# Overview.net
KiCad netlist of a schematic drawn in Altium Designer
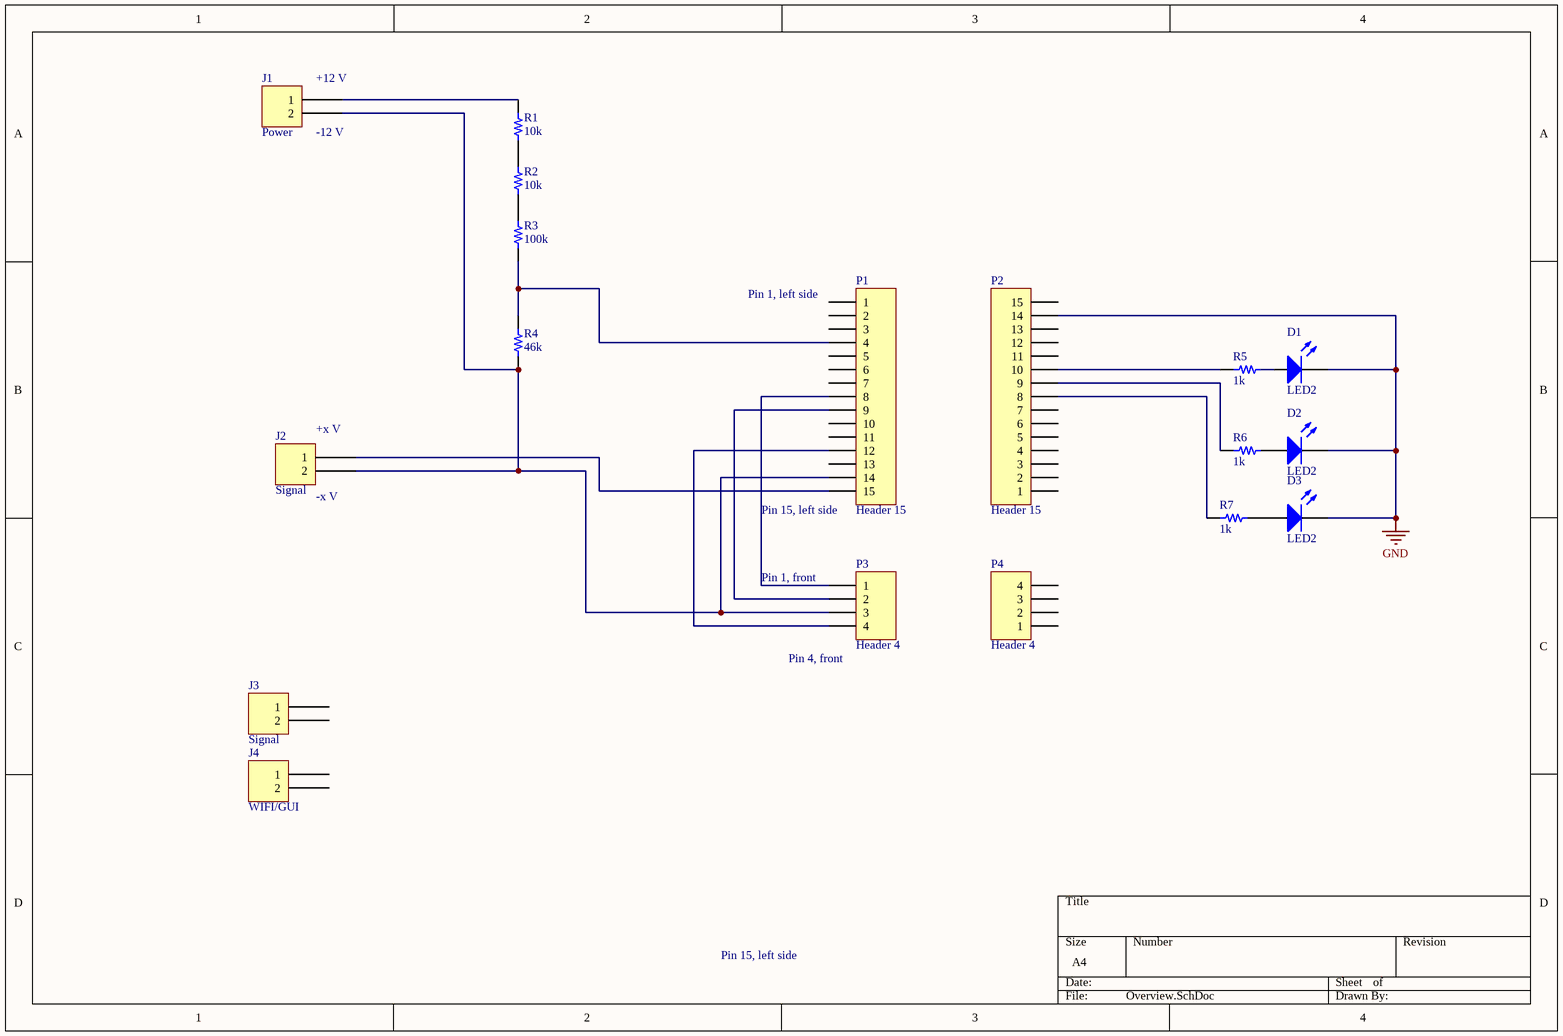
[diagram p0: Overview.SchDoc]

(export (version "E")
  (design (tool "Eeschema 10.0.6"))
  (components
    (comp (ref "D1")
      (value "LED2")
      (footprint "3.2X1.6X1.1")
      (description "RED")
      (fields (field (name "PUBLISHER") "Altium Limited"))
      (libsource (lib "Miscellaneous Devices") (part "LED2"))
    )
    (comp (ref "D2")
      (value "LED2")
      (footprint "3.2X1.6X1.1")
      (description "GREEN")
      (fields (field (name "PUBLISHER") "Altium Limited"))
      (libsource (lib "Miscellaneous Devices") (part "LED2"))
    )
    (comp (ref "D3")
      (value "LED2")
      (footprint "3.2X1.6X1.1")
      (description "YELLOW")
      (fields (field (name "PUBLISHER") "Altium Limited"))
      (libsource (lib "Miscellaneous Devices") (part "LED2"))
    )
    (comp (ref "J1")
      (value "Power")
      (footprint "JST XH B2B-XH-A")
      (description "CONN HEADER XH TOP 2POS 2.5MM")
      (fields
        (field (name "PART NUMBER") "B2B-XH-A(LF)(SN)")
        (field (name "MANUFACTURER") "JST Sales America Inc.")
      )
      (libsource (lib "Celestial Library Database") (part "2 Pin"))
    )
    (comp (ref "J2")
      (value "Signal")
      (footprint "JST XH B2B-XH-A")
      (description "CONN HEADER XH TOP 2POS 2.5MM")
      (fields
        (field (name "PART NUMBER") "B2B-XH-A(LF)(SN)")
        (field (name "MANUFACTURER") "JST Sales America Inc.")
      )
      (libsource (lib "Celestial Library Database") (part "2 Pin"))
    )
    (comp (ref "J3")
      (value "Signal")
      (footprint "JST XH B2B-XH-A")
      (description "CONN HEADER XH TOP 2POS 2.5MM")
      (fields
        (field (name "PART NUMBER") "B2B-XH-A(LF)(SN)")
        (field (name "MANUFACTURER") "JST Sales America Inc.")
      )
      (libsource (lib "Celestial Library Database") (part "2 Pin"))
    )
    (comp (ref "J4")
      (value "WIFI/GUI")
      (footprint "JST XH B2B-XH-A")
      (description "CONN HEADER XH TOP 2POS 2.5MM")
      (fields
        (field (name "PART NUMBER") "B2B-XH-A(LF)(SN)")
        (field (name "MANUFACTURER") "JST Sales America Inc.")
      )
      (libsource (lib "Celestial Library Database") (part "2 Pin"))
    )
    (comp (ref "P1")
      (value "Header 15")
      (footprint "HDR1X15")
      (description "Header, 15-Pin")
      (fields (field (name "PUBLISHER") "Altium Limited"))
      (libsource (lib "Miscellaneous Connectors") (part "Header 15"))
    )
    (comp (ref "P2")
      (value "Header 15")
      (footprint "HDR1X15")
      (description "Header, 15-Pin")
      (fields (field (name "PUBLISHER") "Altium Limited"))
      (libsource (lib "") (part "Header 15_1"))
    )
    (comp (ref "P3")
      (value "Header 4")
      (footprint "HDR1X4")
      (description "Header, 4-Pin")
      (fields (field (name "PUBLISHER") "Altium Limited"))
      (libsource (lib "") (part "Header 4_1"))
    )
    (comp (ref "P4")
      (value "Header 4")
      (footprint "HDR1X4")
      (description "Header, 4-Pin")
      (fields (field (name "PUBLISHER") "Altium Limited"))
      (libsource (lib "Miscellaneous Connectors") (part "Header 4"))
    )
    (comp (ref "R1")
      (value "10k")
      (footprint "RES 0805/2012")
      (description "RES SMD 100K OHM 5% 1/8W 0805")
      (fields
        (field (name "PART NUMBER") "ERJ-6GEYJ104V")
        (field (name "MANUFACTURER") "Panasonic Electronic Components")
      )
      (libsource (lib "Celestial Library Database") (part "Resistor"))
    )
    (comp (ref "R2")
      (value "10k")
      (footprint "RES 0805/2012")
      (description "RES SMD 100K OHM 5% 1/8W 0805")
      (fields
        (field (name "PART NUMBER") "ERJ-6GEYJ104V")
        (field (name "MANUFACTURER") "Panasonic Electronic Components")
      )
      (libsource (lib "Celestial Library Database") (part "Resistor"))
    )
    (comp (ref "R3")
      (value "100k")
      (footprint "RES 0805/2012")
      (description "RES SMD 100K OHM 5% 1/8W 0805")
      (fields
        (field (name "PART NUMBER") "ERJ-6GEYJ104V")
        (field (name "MANUFACTURER") "Panasonic Electronic Components")
      )
      (libsource (lib "Celestial Library Database") (part "Resistor"))
    )
    (comp (ref "R4")
      (value "46k")
      (footprint "RES 0805/2012")
      (description "RES SMD 100K OHM 5% 1/8W 0805")
      (fields
        (field (name "PART NUMBER") "ERJ-6GEYJ104V")
        (field (name "MANUFACTURER") "Panasonic Electronic Components")
      )
      (libsource (lib "Celestial Library Database") (part "Resistor"))
    )
    (comp (ref "R5")
      (value "1k")
      (footprint "RES 0805/2012")
      (description "RES SMD 100K OHM 5% 1/8W 0805")
      (fields
        (field (name "PART NUMBER") "ERJ-6GEYJ104V")
        (field (name "MANUFACTURER") "Panasonic Electronic Components")
      )
      (libsource (lib "Celestial Library Database") (part "Resistor"))
    )
    (comp (ref "R6")
      (value "1k")
      (footprint "RES 0805/2012")
      (description "RES SMD 100K OHM 5% 1/8W 0805")
      (fields
        (field (name "PART NUMBER") "ERJ-6GEYJ104V")
        (field (name "MANUFACTURER") "Panasonic Electronic Components")
      )
      (libsource (lib "Celestial Library Database") (part "Resistor"))
    )
    (comp (ref "R7")
      (value "1k")
      (footprint "RES 0805/2012")
      (description "RES SMD 100K OHM 5% 1/8W 0805")
      (fields
        (field (name "PART NUMBER") "ERJ-6GEYJ104V")
        (field (name "MANUFACTURER") "Panasonic Electronic Components")
      )
      (libsource (lib "Celestial Library Database") (part "Resistor"))
    )
  )
  (nets
    (net (code "1") (name "GND") (class "Default")
      (node (ref "D1") (pin "2") (pinfunction "K_2") (pintype "passive"))
      (node (ref "D2") (pin "2") (pinfunction "K_2") (pintype "passive"))
      (node (ref "D3") (pin "2") (pinfunction "K_2") (pintype "passive"))
      (node (ref "P2") (pin "14") (pinfunction "14_14") (pintype "passive"))
    )
    (net (code "2") (name "Net-(D1-A)") (class "Default")
      (node (ref "D1") (pin "1") (pinfunction "A_1") (pintype "passive"))
      (node (ref "R5") (pin "2") (pinfunction "2_2") (pintype "passive"))
    )
    (net (code "3") (name "Net-(D3-A)") (class "Default")
      (node (ref "D3") (pin "1") (pinfunction "A_1") (pintype "passive"))
      (node (ref "R7") (pin "2") (pinfunction "2_2") (pintype "passive"))
    )
    (net (code "4") (name "Net-(J1-Pad1)") (class "Default")
      (node (ref "J1") (pin "1") (pinfunction "1_1") (pintype "passive"))
      (node (ref "R1") (pin "2") (pinfunction "2_2") (pintype "passive"))
    )
    (net (code "5") (name "Net-(J1-Pad2)") (class "Default")
      (node (ref "J1") (pin "2") (pinfunction "2_2") (pintype "passive"))
      (node (ref "J2") (pin "2") (pinfunction "2_2") (pintype "passive"))
      (node (ref "P1") (pin "14") (pinfunction "14_14") (pintype "passive"))
      (node (ref "P3") (pin "3") (pinfunction "3_3") (pintype "passive"))
      (node (ref "R4") (pin "1") (pinfunction "1_1") (pintype "passive"))
    )
    (net (code "6") (name "Net-(J2-Pad1)") (class "Default")
      (node (ref "J2") (pin "1") (pinfunction "1_1") (pintype "passive"))
      (node (ref "P1") (pin "15") (pinfunction "15_15") (pintype "passive"))
    )
    (net (code "7") (name "Net-(P1-Pad4)") (class "Default")
      (node (ref "P1") (pin "4") (pinfunction "4_4") (pintype "passive"))
      (node (ref "R3") (pin "1") (pinfunction "1_1") (pintype "passive"))
      (node (ref "R4") (pin "2") (pinfunction "2_2") (pintype "passive"))
    )
    (net (code "8") (name "Net-(P1-Pad8)") (class "Default")
      (node (ref "P1") (pin "8") (pinfunction "8_8") (pintype "passive"))
      (node (ref "P3") (pin "1") (pinfunction "1_1") (pintype "passive"))
    )
    (net (code "9") (name "Net-(P1-Pad9)") (class "Default")
      (node (ref "P1") (pin "9") (pinfunction "9_9") (pintype "passive"))
      (node (ref "P3") (pin "2") (pinfunction "2_2") (pintype "passive"))
    )
    (net (code "10") (name "Net-(P1-Pad12)") (class "Default")
      (node (ref "P1") (pin "12") (pinfunction "12_12") (pintype "passive"))
      (node (ref "P3") (pin "4") (pinfunction "4_4") (pintype "passive"))
    )
    (net (code "11") (name "Net-(P2-Pad8)") (class "Default")
      (node (ref "P2") (pin "8") (pinfunction "8_8") (pintype "passive"))
      (node (ref "R7") (pin "1") (pinfunction "1_1") (pintype "passive"))
    )
    (net (code "12") (name "Net-(P2-Pad9)") (class "Default")
      (node (ref "P2") (pin "9") (pinfunction "9_9") (pintype "passive"))
      (node (ref "R6") (pin "1") (pinfunction "1_1") (pintype "passive"))
    )
    (net (code "13") (name "Net-(P2-Pad10)") (class "Default")
      (node (ref "P2") (pin "10") (pinfunction "10_10") (pintype "passive"))
      (node (ref "R5") (pin "1") (pinfunction "1_1") (pintype "passive"))
    )
    (net (code "14") (name "Net-(R1-Pad1)") (class "Default")
      (node (ref "R1") (pin "1") (pinfunction "1_1") (pintype "passive"))
      (node (ref "R2") (pin "2") (pinfunction "2_2") (pintype "passive"))
    )
    (net (code "15") (name "Net-(R2-Pad1)") (class "Default")
      (node (ref "R2") (pin "1") (pinfunction "1_1") (pintype "passive"))
      (node (ref "R3") (pin "2") (pinfunction "2_2") (pintype "passive"))
    )
    (net (code "16") (name "unconnected-(D2-A-Pad1)") (class "Default")
      (node (ref "D2") (pin "1") (pinfunction "A_1") (pintype "passive"))
    )
    (net (code "17") (name "unconnected-(J3-Pad1)") (class "Default")
      (node (ref "J3") (pin "1") (pinfunction "1_1") (pintype "passive"))
    )
    (net (code "18") (name "unconnected-(J3-Pad2)") (class "Default")
      (node (ref "J3") (pin "2") (pinfunction "2_2") (pintype "passive"))
    )
    (net (code "19") (name "unconnected-(J4-Pad1)") (class "Default")
      (node (ref "J4") (pin "1") (pinfunction "1_1") (pintype "passive"))
    )
    (net (code "20") (name "unconnected-(J4-Pad2)") (class "Default")
      (node (ref "J4") (pin "2") (pinfunction "2_2") (pintype "passive"))
    )
    (net (code "21") (name "unconnected-(P1-Pad1)") (class "Default")
      (node (ref "P1") (pin "1") (pinfunction "1_1") (pintype "passive"))
    )
    (net (code "22") (name "unconnected-(P1-Pad2)") (class "Default")
      (node (ref "P1") (pin "2") (pinfunction "2_2") (pintype "passive"))
    )
    (net (code "23") (name "unconnected-(P1-Pad3)") (class "Default")
      (node (ref "P1") (pin "3") (pinfunction "3_3") (pintype "passive"))
    )
    (net (code "24") (name "unconnected-(P1-Pad5)") (class "Default")
      (node (ref "P1") (pin "5") (pinfunction "5_5") (pintype "passive"))
    )
    (net (code "25") (name "unconnected-(P1-Pad6)") (class "Default")
      (node (ref "P1") (pin "6") (pinfunction "6_6") (pintype "passive"))
    )
    (net (code "26") (name "unconnected-(P1-Pad7)") (class "Default")
      (node (ref "P1") (pin "7") (pinfunction "7_7") (pintype "passive"))
    )
    (net (code "27") (name "unconnected-(P1-Pad10)") (class "Default")
      (node (ref "P1") (pin "10") (pinfunction "10_10") (pintype "passive"))
    )
    (net (code "28") (name "unconnected-(P1-Pad11)") (class "Default")
      (node (ref "P1") (pin "11") (pinfunction "11_11") (pintype "passive"))
    )
    (net (code "29") (name "unconnected-(P1-Pad13)") (class "Default")
      (node (ref "P1") (pin "13") (pinfunction "13_13") (pintype "passive"))
    )
    (net (code "30") (name "unconnected-(P2-Pad1)") (class "Default")
      (node (ref "P2") (pin "1") (pinfunction "1_1") (pintype "passive"))
    )
    (net (code "31") (name "unconnected-(P2-Pad2)") (class "Default")
      (node (ref "P2") (pin "2") (pinfunction "2_2") (pintype "passive"))
    )
    (net (code "32") (name "unconnected-(P2-Pad3)") (class "Default")
      (node (ref "P2") (pin "3") (pinfunction "3_3") (pintype "passive"))
    )
    (net (code "33") (name "unconnected-(P2-Pad4)") (class "Default")
      (node (ref "P2") (pin "4") (pinfunction "4_4") (pintype "passive"))
    )
    (net (code "34") (name "unconnected-(P2-Pad5)") (class "Default")
      (node (ref "P2") (pin "5") (pinfunction "5_5") (pintype "passive"))
    )
    (net (code "35") (name "unconnected-(P2-Pad6)") (class "Default")
      (node (ref "P2") (pin "6") (pinfunction "6_6") (pintype "passive"))
    )
    (net (code "36") (name "unconnected-(P2-Pad7)") (class "Default")
      (node (ref "P2") (pin "7") (pinfunction "7_7") (pintype "passive"))
    )
    (net (code "37") (name "unconnected-(P2-Pad11)") (class "Default")
      (node (ref "P2") (pin "11") (pinfunction "11_11") (pintype "passive"))
    )
    (net (code "38") (name "unconnected-(P2-Pad12)") (class "Default")
      (node (ref "P2") (pin "12") (pinfunction "12_12") (pintype "passive"))
    )
    (net (code "39") (name "unconnected-(P2-Pad13)") (class "Default")
      (node (ref "P2") (pin "13") (pinfunction "13_13") (pintype "passive"))
    )
    (net (code "40") (name "unconnected-(P2-Pad15)") (class "Default")
      (node (ref "P2") (pin "15") (pinfunction "15_15") (pintype "passive"))
    )
    (net (code "41") (name "unconnected-(P4-Pad1)") (class "Default")
      (node (ref "P4") (pin "1") (pinfunction "1_1") (pintype "passive"))
    )
    (net (code "42") (name "unconnected-(P4-Pad2)") (class "Default")
      (node (ref "P4") (pin "2") (pinfunction "2_2") (pintype "passive"))
    )
    (net (code "43") (name "unconnected-(P4-Pad3)") (class "Default")
      (node (ref "P4") (pin "3") (pinfunction "3_3") (pintype "passive"))
    )
    (net (code "44") (name "unconnected-(P4-Pad4)") (class "Default")
      (node (ref "P4") (pin "4") (pinfunction "4_4") (pintype "passive"))
    )
    (net (code "45") (name "unconnected-(R6-Pad2)") (class "Default")
      (node (ref "R6") (pin "2") (pinfunction "2_2") (pintype "passive"))
    )
  )
)
